# design.net
KiCad netlist of a schematic drawn in Altium Designer
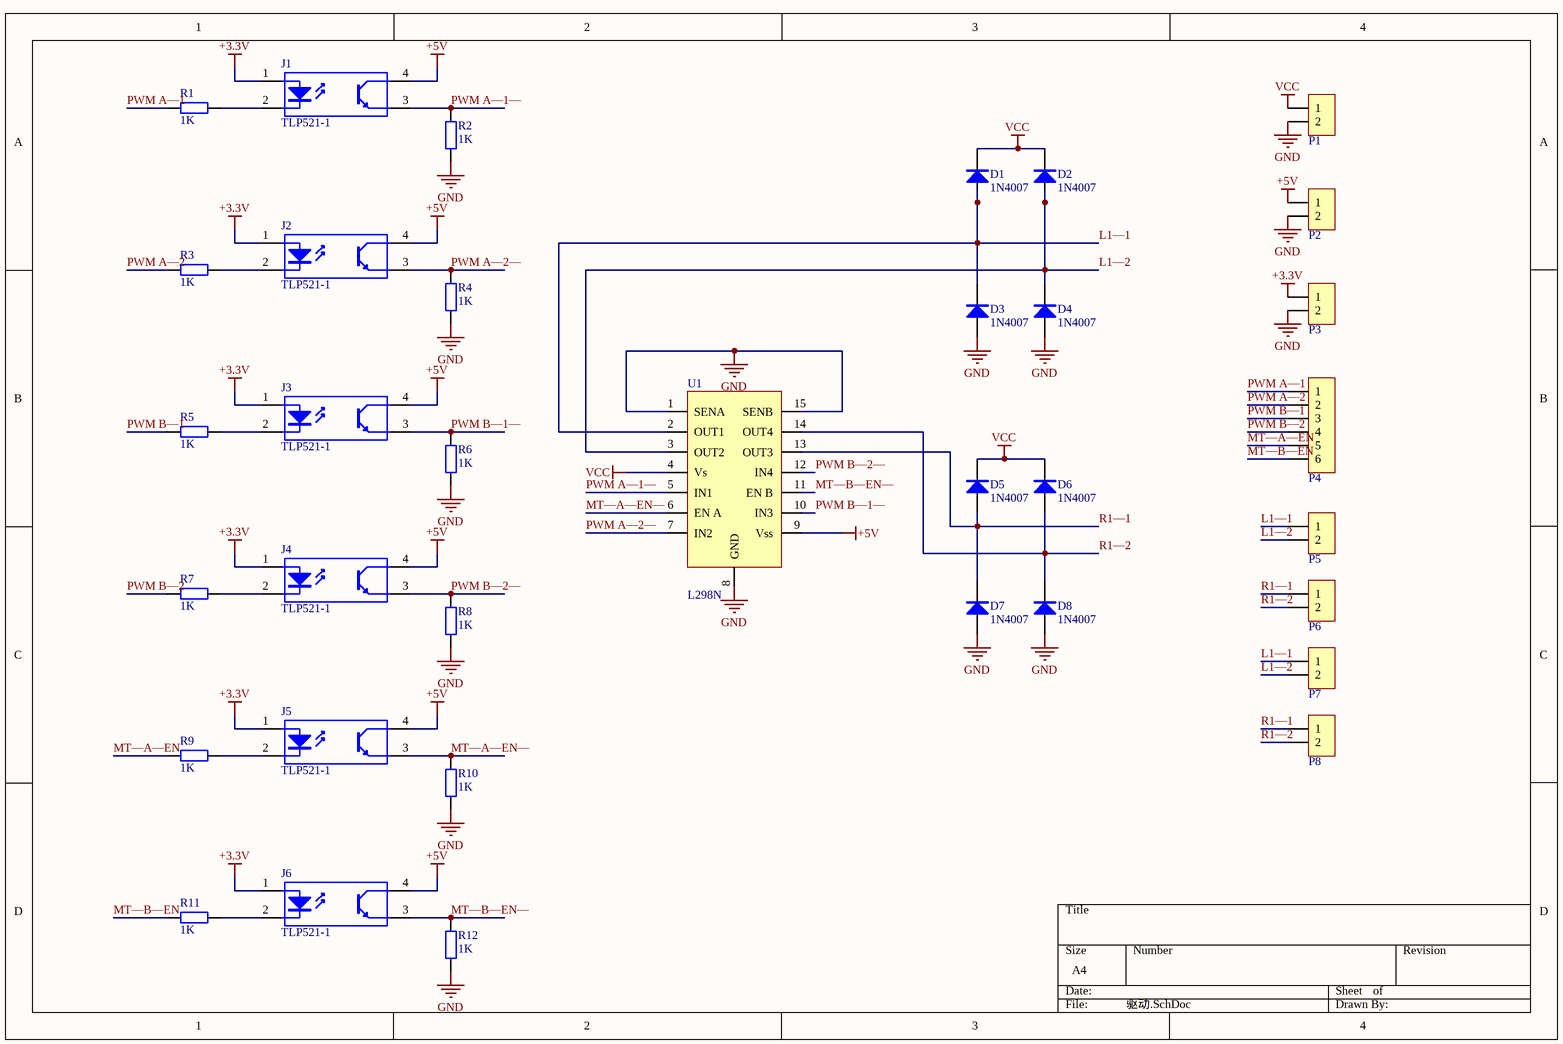
[diagram p0: 驱动.SchDoc]

(export (version "E")
  (design (tool "Eeschema 10.0.6"))
  (components
    (comp (ref "D1")
      (value "1N4007")
      (footprint "SOD-123")
      (description "整流二极管")
      (libsource (lib "0.2 - 二极管-整流桥") (part "1N4007"))
    )
    (comp (ref "D2")
      (value "1N4007")
      (footprint "SOD-123")
      (description "整流二极管")
      (libsource (lib "0.2 - 二极管-整流桥") (part "1N4007"))
    )
    (comp (ref "D3")
      (value "1N4007")
      (footprint "SOD-123")
      (description "整流二极管")
      (libsource (lib "0.2 - 二极管-整流桥") (part "1N4007"))
    )
    (comp (ref "D4")
      (value "1N4007")
      (footprint "SOD-123")
      (description "整流二极管")
      (libsource (lib "0.2 - 二极管-整流桥") (part "1N4007"))
    )
    (comp (ref "D5")
      (value "1N4007")
      (footprint "SOD-123")
      (description "整流二极管")
      (libsource (lib "0.2 - 二极管-整流桥") (part "1N4007"))
    )
    (comp (ref "D6")
      (value "1N4007")
      (footprint "SOD-123")
      (description "整流二极管")
      (libsource (lib "0.2 - 二极管-整流桥") (part "1N4007"))
    )
    (comp (ref "D7")
      (value "1N4007")
      (footprint "SOD-123")
      (description "整流二极管")
      (libsource (lib "0.2 - 二极管-整流桥") (part "1N4007"))
    )
    (comp (ref "D8")
      (value "1N4007")
      (footprint "SOD-123")
      (description "整流二极管")
      (libsource (lib "0.2 - 二极管-整流桥") (part "1N4007"))
    )
    (comp (ref "J1")
      (value "TLP521-1")
      (footprint "DIP4-300")
      (description "1路开关光耦")
      (fields (field (name "版权归属") "封装库来自淘宝 ID：黄晶宝石"))
      (libsource (lib "1.2 - 传感元件") (part "TLP521-1"))
    )
    (comp (ref "J2")
      (value "TLP521-1")
      (footprint "DIP4-300")
      (description "1路开关光耦")
      (fields (field (name "版权归属") "封装库来自淘宝 ID：黄晶宝石"))
      (libsource (lib "1.2 - 传感元件") (part "TLP521-1"))
    )
    (comp (ref "J3")
      (value "TLP521-1")
      (footprint "DIP4-300")
      (description "1路开关光耦")
      (fields (field (name "版权归属") "封装库来自淘宝 ID：黄晶宝石"))
      (libsource (lib "1.2 - 传感元件") (part "TLP521-1"))
    )
    (comp (ref "J4")
      (value "TLP521-1")
      (footprint "DIP4-300")
      (description "1路开关光耦")
      (fields (field (name "版权归属") "封装库来自淘宝 ID：黄晶宝石"))
      (libsource (lib "1.2 - 传感元件") (part "TLP521-1"))
    )
    (comp (ref "J5")
      (value "TLP521-1")
      (footprint "DIP4-300")
      (description "1路开关光耦")
      (fields (field (name "版权归属") "封装库来自淘宝 ID：黄晶宝石"))
      (libsource (lib "1.2 - 传感元件") (part "TLP521-1"))
    )
    (comp (ref "J6")
      (value "TLP521-1")
      (footprint "DIP4-300")
      (description "1路开关光耦")
      (fields (field (name "版权归属") "封装库来自淘宝 ID：黄晶宝石"))
      (libsource (lib "1.2 - 传感元件") (part "TLP521-1"))
    )
    (comp (ref "P1")
      (value "HDR-1X2")
      (footprint "KF128-3.81-2P")
      (description "2P接插件")
      (fields (field (name "版权归属") "封装库来自淘宝 ID：黄晶宝石"))
      (libsource (lib "6.0 - 接插件-脚距5.0") (part "Header 2"))
    )
    (comp (ref "P2")
      (value "HDR-1X2")
      (footprint "HDR1X2")
      (description "2P接插件")
      (fields (field (name "版权归属") "封装库来自淘宝 ID：黄晶宝石"))
      (libsource (lib "6.0 - 接插件-脚距5.0") (part "Header 2"))
    )
    (comp (ref "P3")
      (value "HDR-1X2")
      (footprint "HDR1X2")
      (description "2P接插件")
      (fields (field (name "版权归属") "封装库来自淘宝 ID：黄晶宝石"))
      (libsource (lib "6.0 - 接插件-脚距5.0") (part "Header 2"))
    )
    (comp (ref "P4")
      (value "HDR-1X6")
      (footprint "HDR1X6")
      (description "6P接插件")
      (fields (field (name "版权归属") "封装库来自淘宝 ID：黄晶宝石"))
      (libsource (lib "6.0 - 接插件-脚距5.0") (part "Header 6"))
    )
    (comp (ref "P5")
      (value "HDR-1X2")
      (footprint "KF128-3.81-2P")
      (description "2P接插件")
      (fields (field (name "版权归属") "封装库来自淘宝 ID：黄晶宝石"))
      (libsource (lib "6.0 - 接插件-脚距5.0") (part "Header 2"))
    )
    (comp (ref "P6")
      (value "HDR-1X2")
      (footprint "KF128-3.81-2P")
      (description "2P接插件")
      (fields (field (name "版权归属") "封装库来自淘宝 ID：黄晶宝石"))
      (libsource (lib "6.0 - 接插件-脚距5.0") (part "Header 2"))
    )
    (comp (ref "P7")
      (value "HDR-1X2")
      (footprint "KF128-3.81-2P")
      (description "2P接插件")
      (fields (field (name "版权归属") "封装库来自淘宝 ID：黄晶宝石"))
      (libsource (lib "6.0 - 接插件-脚距5.0") (part "Header 2"))
    )
    (comp (ref "P8")
      (value "HDR-1X2")
      (footprint "KF128-3.81-2P")
      (description "2P接插件")
      (fields (field (name "版权归属") "封装库来自淘宝 ID：黄晶宝石"))
      (libsource (lib "6.0 - 接插件-脚距5.0") (part "Header 2"))
    )
    (comp (ref "R1")
      (value "1K")
      (footprint "R 0805_L")
      (description "贴片电阻")
      (fields (field (name "版权归属") "来自淘宝 ID：黄晶宝石"))
      (libsource (lib "0.1 - 电阻-电容-电感") (part "R"))
    )
    (comp (ref "R2")
      (value "1K")
      (footprint "R 0805_L")
      (description "贴片电阻")
      (fields (field (name "版权归属") "来自淘宝 ID：黄晶宝石"))
      (libsource (lib "0.1 - 电阻-电容-电感") (part "R"))
    )
    (comp (ref "R3")
      (value "1K")
      (footprint "R 0805_L")
      (description "贴片电阻")
      (fields (field (name "版权归属") "来自淘宝 ID：黄晶宝石"))
      (libsource (lib "0.1 - 电阻-电容-电感") (part "R"))
    )
    (comp (ref "R4")
      (value "1K")
      (footprint "R 0805_L")
      (description "贴片电阻")
      (fields (field (name "版权归属") "来自淘宝 ID：黄晶宝石"))
      (libsource (lib "0.1 - 电阻-电容-电感") (part "R"))
    )
    (comp (ref "R5")
      (value "1K")
      (footprint "R 0805_L")
      (description "贴片电阻")
      (fields (field (name "版权归属") "来自淘宝 ID：黄晶宝石"))
      (libsource (lib "0.1 - 电阻-电容-电感") (part "R"))
    )
    (comp (ref "R6")
      (value "1K")
      (footprint "R 0805_L")
      (description "贴片电阻")
      (fields (field (name "版权归属") "来自淘宝 ID：黄晶宝石"))
      (libsource (lib "0.1 - 电阻-电容-电感") (part "R"))
    )
    (comp (ref "R7")
      (value "1K")
      (footprint "R 0805_L")
      (description "贴片电阻")
      (fields (field (name "版权归属") "来自淘宝 ID：黄晶宝石"))
      (libsource (lib "0.1 - 电阻-电容-电感") (part "R"))
    )
    (comp (ref "R8")
      (value "1K")
      (footprint "R 0805_L")
      (description "贴片电阻")
      (fields (field (name "版权归属") "来自淘宝 ID：黄晶宝石"))
      (libsource (lib "0.1 - 电阻-电容-电感") (part "R"))
    )
    (comp (ref "R9")
      (value "1K")
      (footprint "R 0805_L")
      (description "贴片电阻")
      (fields (field (name "版权归属") "来自淘宝 ID：黄晶宝石"))
      (libsource (lib "0.1 - 电阻-电容-电感") (part "R"))
    )
    (comp (ref "R10")
      (value "1K")
      (footprint "R 0805_L")
      (description "贴片电阻")
      (fields (field (name "版权归属") "来自淘宝 ID：黄晶宝石"))
      (libsource (lib "0.1 - 电阻-电容-电感") (part "R"))
    )
    (comp (ref "R11")
      (value "1K")
      (footprint "R 0805_L")
      (description "贴片电阻")
      (fields (field (name "版权归属") "来自淘宝 ID：黄晶宝石"))
      (libsource (lib "0.1 - 电阻-电容-电感") (part "R"))
    )
    (comp (ref "R12")
      (value "1K")
      (footprint "R 0805_L")
      (description "贴片电阻")
      (fields (field (name "版权归属") "来自淘宝 ID：黄晶宝石"))
      (libsource (lib "0.1 - 电阻-电容-电感") (part "R"))
    )
    (comp (ref "U1")
      (value "L298N")
      (footprint "Multiwatt15-V")
      (libsource (lib "1.0 - 常见芯片") (part "L298N"))
    )
  )
  (nets
    (net (code "1") (name "+3.3V") (class "Default")
      (node (ref "J1") (pin "1") (pinfunction "A_1") (pintype "passive"))
      (node (ref "J2") (pin "1") (pinfunction "A_1") (pintype "passive"))
      (node (ref "J3") (pin "1") (pinfunction "A_1") (pintype "passive"))
      (node (ref "J4") (pin "1") (pinfunction "A_1") (pintype "passive"))
      (node (ref "J5") (pin "1") (pinfunction "A_1") (pintype "passive"))
      (node (ref "J6") (pin "1") (pinfunction "A_1") (pintype "passive"))
      (node (ref "P3") (pin "1") (pinfunction "1_1") (pintype "passive"))
    )
    (net (code "2") (name "+5V") (class "Default")
      (node (ref "J1") (pin "4") (pinfunction "C_4") (pintype "passive"))
      (node (ref "J2") (pin "4") (pinfunction "C_4") (pintype "passive"))
      (node (ref "J3") (pin "4") (pinfunction "C_4") (pintype "passive"))
      (node (ref "J4") (pin "4") (pinfunction "C_4") (pintype "passive"))
      (node (ref "J5") (pin "4") (pinfunction "C_4") (pintype "passive"))
      (node (ref "J6") (pin "4") (pinfunction "C_4") (pintype "passive"))
      (node (ref "P2") (pin "1") (pinfunction "1_1") (pintype "passive"))
      (node (ref "U1") (pin "9") (pinfunction "Vss_9") (pintype "passive"))
    )
    (net (code "3") (name "/L1—1") (class "Default")
      (node (ref "D1") (pin "1") (pinfunction "A_1") (pintype "passive"))
      (node (ref "D3") (pin "2") (pinfunction "K_2") (pintype "passive"))
      (node (ref "P5") (pin "1") (pinfunction "1_1") (pintype "passive"))
      (node (ref "P7") (pin "1") (pinfunction "1_1") (pintype "passive"))
      (node (ref "U1") (pin "2") (pinfunction "OUT1_2") (pintype "passive"))
    )
    (net (code "4") (name "/L1—2") (class "Default")
      (node (ref "D2") (pin "1") (pinfunction "A_1") (pintype "passive"))
      (node (ref "D4") (pin "2") (pinfunction "K_2") (pintype "passive"))
      (node (ref "P5") (pin "2") (pinfunction "2_2") (pintype "passive"))
      (node (ref "P7") (pin "2") (pinfunction "2_2") (pintype "passive"))
      (node (ref "U1") (pin "3") (pinfunction "OUT2_3") (pintype "passive"))
    )
    (net (code "5") (name "/MT—A—EN") (class "Default")
      (node (ref "P4") (pin "5") (pinfunction "5_5") (pintype "passive"))
      (node (ref "R9") (pin "1") (pinfunction "1_1") (pintype "passive"))
    )
    (net (code "6") (name "/MT—A—EN—") (class "Default")
      (node (ref "J5") (pin "3") (pinfunction "E_3") (pintype "passive"))
      (node (ref "R10") (pin "2") (pinfunction "2_2") (pintype "passive"))
      (node (ref "U1") (pin "6") (pinfunction "EN_A_6") (pintype "passive"))
    )
    (net (code "7") (name "/MT—B—EN") (class "Default")
      (node (ref "P4") (pin "6") (pinfunction "6_6") (pintype "passive"))
      (node (ref "R11") (pin "1") (pinfunction "1_1") (pintype "passive"))
    )
    (net (code "8") (name "/MT—B—EN—") (class "Default")
      (node (ref "J6") (pin "3") (pinfunction "E_3") (pintype "passive"))
      (node (ref "R12") (pin "2") (pinfunction "2_2") (pintype "passive"))
      (node (ref "U1") (pin "11") (pinfunction "EN_B_11") (pintype "passive"))
    )
    (net (code "9") (name "/PWM A—1") (class "Default")
      (node (ref "P4") (pin "1") (pinfunction "1_1") (pintype "passive"))
      (node (ref "R1") (pin "1") (pinfunction "1_1") (pintype "passive"))
    )
    (net (code "10") (name "/PWM A—1—") (class "Default")
      (node (ref "J1") (pin "3") (pinfunction "E_3") (pintype "passive"))
      (node (ref "R2") (pin "2") (pinfunction "2_2") (pintype "passive"))
      (node (ref "U1") (pin "5") (pinfunction "IN1_5") (pintype "passive"))
    )
    (net (code "11") (name "/PWM A—2") (class "Default")
      (node (ref "P4") (pin "2") (pinfunction "2_2") (pintype "passive"))
      (node (ref "R3") (pin "1") (pinfunction "1_1") (pintype "passive"))
    )
    (net (code "12") (name "/PWM A—2—") (class "Default")
      (node (ref "J2") (pin "3") (pinfunction "E_3") (pintype "passive"))
      (node (ref "R4") (pin "2") (pinfunction "2_2") (pintype "passive"))
      (node (ref "U1") (pin "7") (pinfunction "IN2_7") (pintype "passive"))
    )
    (net (code "13") (name "/PWM B—1") (class "Default")
      (node (ref "P4") (pin "3") (pinfunction "3_3") (pintype "passive"))
      (node (ref "R5") (pin "1") (pinfunction "1_1") (pintype "passive"))
    )
    (net (code "14") (name "/PWM B—1—") (class "Default")
      (node (ref "J3") (pin "3") (pinfunction "E_3") (pintype "passive"))
      (node (ref "R6") (pin "2") (pinfunction "2_2") (pintype "passive"))
      (node (ref "U1") (pin "10") (pinfunction "IN3_10") (pintype "passive"))
    )
    (net (code "15") (name "/PWM B—2") (class "Default")
      (node (ref "P4") (pin "4") (pinfunction "4_4") (pintype "passive"))
      (node (ref "R7") (pin "1") (pinfunction "1_1") (pintype "passive"))
    )
    (net (code "16") (name "/PWM B—2—") (class "Default")
      (node (ref "J4") (pin "3") (pinfunction "E_3") (pintype "passive"))
      (node (ref "R8") (pin "2") (pinfunction "2_2") (pintype "passive"))
      (node (ref "U1") (pin "12") (pinfunction "IN4_12") (pintype "passive"))
    )
    (net (code "17") (name "/R1—1") (class "Default")
      (node (ref "D5") (pin "1") (pinfunction "A_1") (pintype "passive"))
      (node (ref "D7") (pin "2") (pinfunction "K_2") (pintype "passive"))
      (node (ref "P6") (pin "1") (pinfunction "1_1") (pintype "passive"))
      (node (ref "P8") (pin "1") (pinfunction "1_1") (pintype "passive"))
      (node (ref "U1") (pin "13") (pinfunction "OUT3_13") (pintype "passive"))
    )
    (net (code "18") (name "/R1—2") (class "Default")
      (node (ref "D6") (pin "1") (pinfunction "A_1") (pintype "passive"))
      (node (ref "D8") (pin "2") (pinfunction "K_2") (pintype "passive"))
      (node (ref "P6") (pin "2") (pinfunction "2_2") (pintype "passive"))
      (node (ref "P8") (pin "2") (pinfunction "2_2") (pintype "passive"))
      (node (ref "U1") (pin "14") (pinfunction "OUT4_14") (pintype "passive"))
    )
    (net (code "19") (name "GND") (class "Default")
      (node (ref "D3") (pin "1") (pinfunction "A_1") (pintype "passive"))
      (node (ref "D4") (pin "1") (pinfunction "A_1") (pintype "passive"))
      (node (ref "D7") (pin "1") (pinfunction "A_1") (pintype "passive"))
      (node (ref "D8") (pin "1") (pinfunction "A_1") (pintype "passive"))
      (node (ref "P1") (pin "2") (pinfunction "2_2") (pintype "passive"))
      (node (ref "P2") (pin "2") (pinfunction "2_2") (pintype "passive"))
      (node (ref "P3") (pin "2") (pinfunction "2_2") (pintype "passive"))
      (node (ref "R10") (pin "1") (pinfunction "1_1") (pintype "passive"))
      (node (ref "R12") (pin "1") (pinfunction "1_1") (pintype "passive"))
      (node (ref "R2") (pin "1") (pinfunction "1_1") (pintype "passive"))
      (node (ref "R4") (pin "1") (pinfunction "1_1") (pintype "passive"))
      (node (ref "R6") (pin "1") (pinfunction "1_1") (pintype "passive"))
      (node (ref "R8") (pin "1") (pinfunction "1_1") (pintype "passive"))
      (node (ref "U1") (pin "1") (pinfunction "SENA_1") (pintype "passive"))
      (node (ref "U1") (pin "15") (pinfunction "SENB_15") (pintype "passive"))
      (node (ref "U1") (pin "8") (pinfunction "GND_8") (pintype "passive"))
    )
    (net (code "20") (name "Net-(J1-K)") (class "Default")
      (node (ref "J1") (pin "2") (pinfunction "K_2") (pintype "passive"))
      (node (ref "R1") (pin "2") (pinfunction "2_2") (pintype "passive"))
    )
    (net (code "21") (name "Net-(J2-K)") (class "Default")
      (node (ref "J2") (pin "2") (pinfunction "K_2") (pintype "passive"))
      (node (ref "R3") (pin "2") (pinfunction "2_2") (pintype "passive"))
    )
    (net (code "22") (name "Net-(J3-K)") (class "Default")
      (node (ref "J3") (pin "2") (pinfunction "K_2") (pintype "passive"))
      (node (ref "R5") (pin "2") (pinfunction "2_2") (pintype "passive"))
    )
    (net (code "23") (name "Net-(J4-K)") (class "Default")
      (node (ref "J4") (pin "2") (pinfunction "K_2") (pintype "passive"))
      (node (ref "R7") (pin "2") (pinfunction "2_2") (pintype "passive"))
    )
    (net (code "24") (name "Net-(J5-K)") (class "Default")
      (node (ref "J5") (pin "2") (pinfunction "K_2") (pintype "passive"))
      (node (ref "R9") (pin "2") (pinfunction "2_2") (pintype "passive"))
    )
    (net (code "25") (name "Net-(J6-K)") (class "Default")
      (node (ref "J6") (pin "2") (pinfunction "K_2") (pintype "passive"))
      (node (ref "R11") (pin "2") (pinfunction "2_2") (pintype "passive"))
    )
    (net (code "26") (name "VCC") (class "Default")
      (node (ref "D1") (pin "2") (pinfunction "K_2") (pintype "passive"))
      (node (ref "D2") (pin "2") (pinfunction "K_2") (pintype "passive"))
      (node (ref "D5") (pin "2") (pinfunction "K_2") (pintype "passive"))
      (node (ref "D6") (pin "2") (pinfunction "K_2") (pintype "passive"))
      (node (ref "P1") (pin "1") (pinfunction "1_1") (pintype "passive"))
      (node (ref "U1") (pin "4") (pinfunction "Vs_4") (pintype "passive"))
    )
  )
)
